# base.net
KiCad netlist of a schematic drawn in EAGLE
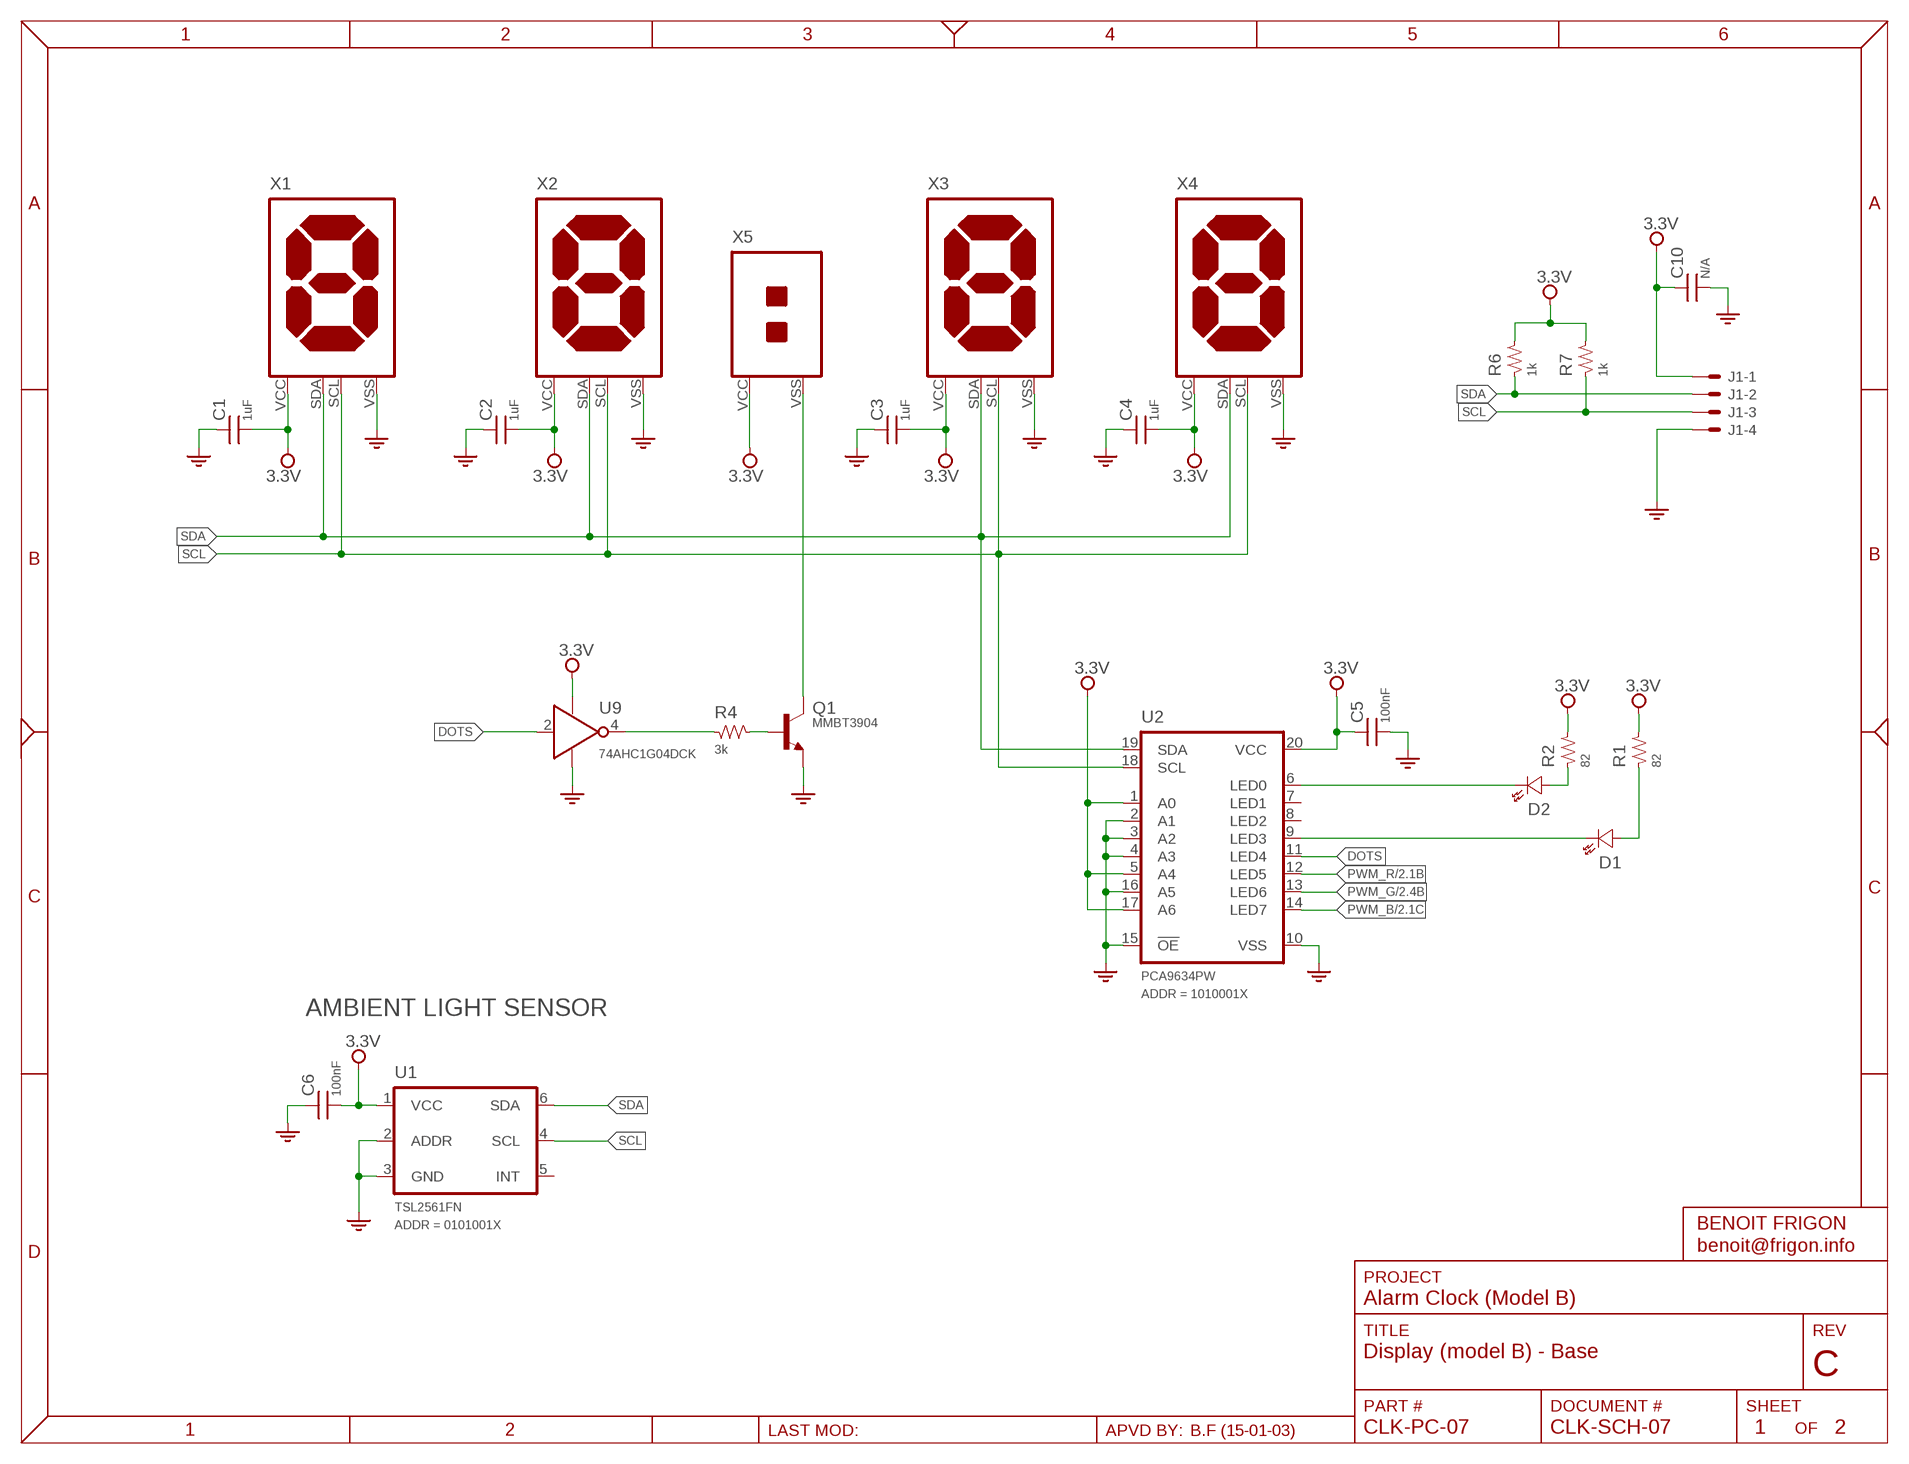
[diagram p0: schematic, sheet 1]
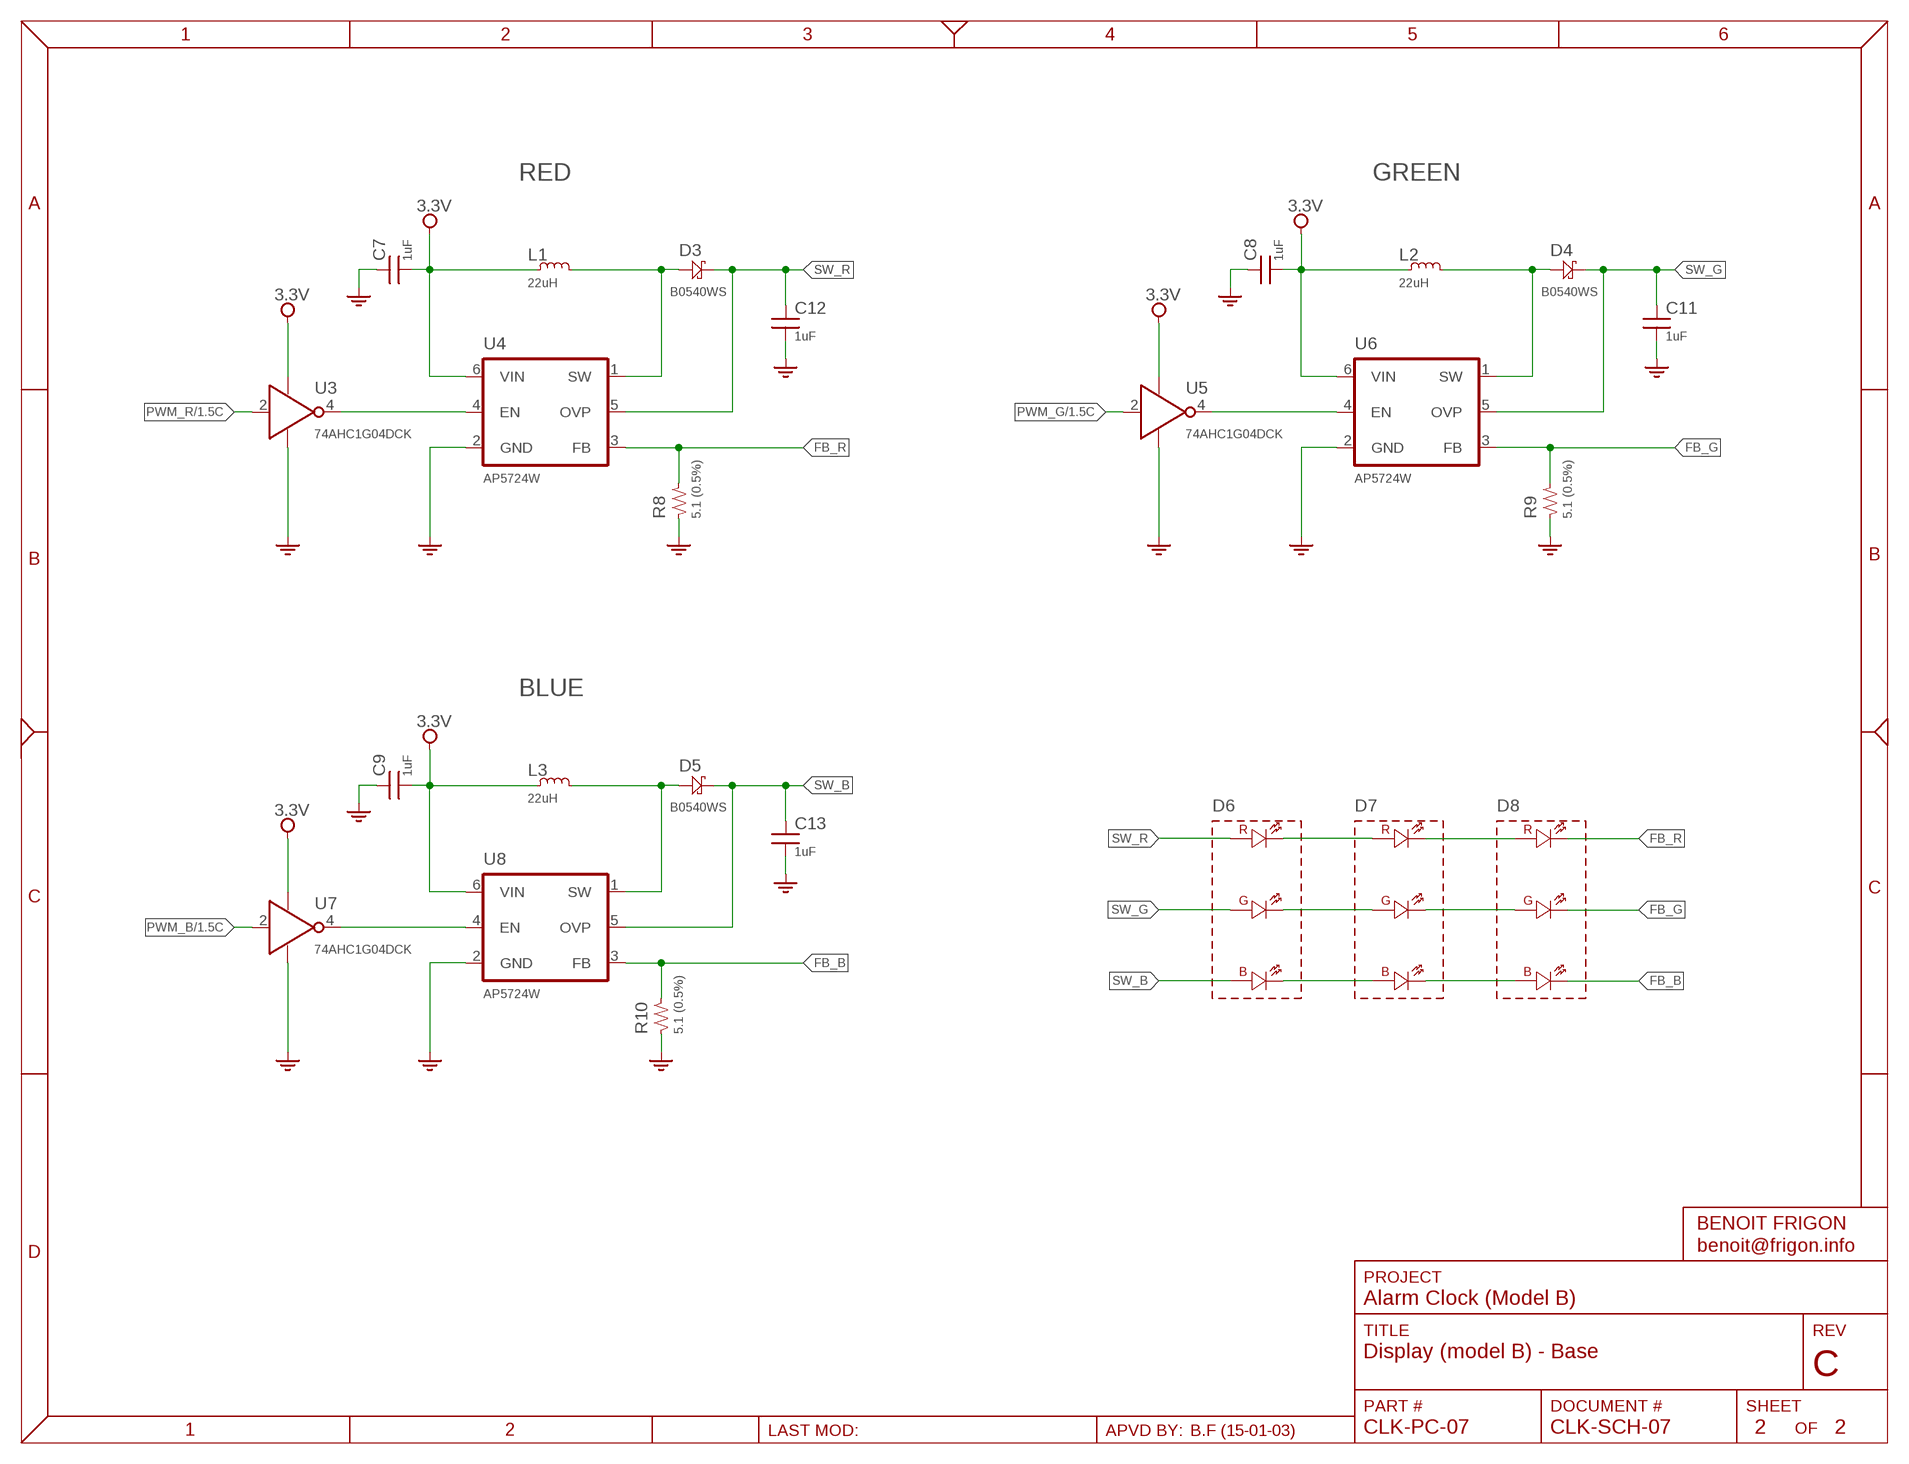
[diagram p1: schematic, sheet 2]

(export (version "E")
  (design (tool "Eeschema 10.0.6"))
  (components
    (comp (ref "C1")
      (value "1uF")
      (footprint "eagle-import:SMD_0603")
      (description "{DESCRIPTION} - SMT 0603 - {value}")
      (fields (field (name "PACKAGE") "SMT 0603"))
      (libsource (lib "eagle-import") (part "CAP-0603"))
    )
    (comp (ref "C2")
      (value "1uF")
      (footprint "eagle-import:SMD_0603")
      (description "{DESCRIPTION} - SMT 0603 - {value}")
      (fields (field (name "PACKAGE") "SMT 0603"))
      (libsource (lib "eagle-import") (part "CAP-0603"))
    )
    (comp (ref "C3")
      (value "1uF")
      (footprint "eagle-import:SMD_0603")
      (description "{DESCRIPTION} - SMT 0603 - {value}")
      (fields (field (name "PACKAGE") "SMT 0603"))
      (libsource (lib "eagle-import") (part "CAP-0603"))
    )
    (comp (ref "C4")
      (value "1uF")
      (footprint "eagle-import:SMD_0603")
      (description "{DESCRIPTION} - SMT 0603 - {value}")
      (fields (field (name "PACKAGE") "SMT 0603"))
      (libsource (lib "eagle-import") (part "CAP-0603"))
    )
    (comp (ref "C5")
      (value "100nF")
      (footprint "eagle-import:SMD_0603")
      (libsource (lib "eagle-import") (part "CAP-0603"))
    )
    (comp (ref "C6")
      (value "100nF")
      (footprint "eagle-import:SMD_0603")
      (libsource (lib "eagle-import") (part "CAP-0603"))
    )
    (comp (ref "C10")
      (value "N/A")
      (footprint "eagle-import:SMD_0805")
      (description "{DESCRIPTION} - SMT 0805 - {value}")
      (fields (field (name "PACKAGE") "SMT 0805"))
      (libsource (lib "eagle-import") (part "CAP-0805"))
    )
    (comp (ref "D1")
      (value "{ATTR:COLOR}")
      (footprint "eagle-import:LED_3MM")
      (description "{DESCRIPTION} T1 (3mm) - {ATTR:COLOR}")
      (fields (field (name "COLOR") "Green") (field (name "PACKAGE") "T1") (field (name "SKU") "-"))
      (libsource (lib "eagle-import") (part "LED-T1"))
    )
    (comp (ref "D2")
      (value "{ATTR:COLOR}")
      (footprint "eagle-import:LED_3MM")
      (libsource (lib "eagle-import") (part "LED-T1"))
    )
    (comp (ref "J1")
      (value "SNG-2MM-HEADER-07-V")
      (footprint "eagle-import:DF3X-7P-2DSA")
      (fields
        (field (name "MFG") "Hirose Electronic")
        (field (name "PART_NO") "DF3A-7P-2DSA")
        (field (name "SKU") "H2099-ND")
        (field (name "PRICE") "0.37")
        (field (name "SUPPLIER") "Digi-Key")
      )
      (libsource (lib "eagle-import") (part "SNG-2MM-HEADER-07-V"))
    )
    (comp (ref "Q1")
      (value "MMBT3904")
      (footprint "eagle-import:SOT23")
      (libsource (lib "eagle-import") (part "MMBT3904"))
    )
    (comp (ref "R1")
      (value "82")
      (footprint "eagle-import:SMD_0603")
      (description "{DESCRIPTION} - SMT 0603 - {VALUE}")
      (fields (field (name "PACKAGE") "SMT 0603"))
      (libsource (lib "eagle-import") (part "RES-0603"))
    )
    (comp (ref "R2")
      (value "82")
      (footprint "eagle-import:SMD_0603")
      (libsource (lib "eagle-import") (part "RES-0603"))
    )
    (comp (ref "R4")
      (value "3k")
      (footprint "eagle-import:SMD_0603")
      (description "{DESCRIPTION} - SMT 0603 - {VALUE}")
      (fields (field (name "PACKAGE") "SMT 0603"))
      (libsource (lib "eagle-import") (part "RES-0603"))
    )
    (comp (ref "R6")
      (value "1k")
      (footprint "eagle-import:SMD_0603")
      (libsource (lib "eagle-import") (part "RES-0603"))
    )
    (comp (ref "R7")
      (value "1k")
      (footprint "eagle-import:SMD_0603")
      (libsource (lib "eagle-import") (part "RES-0603"))
    )
    (comp (ref "U1")
      (value "TSL2561FN")
      (footprint "eagle-import:DFN-6")
      (fields (field (name "ADDR") "0101001X"))
      (libsource (lib "eagle-import") (part "TSL2561FN"))
    )
    (comp (ref "U2")
      (value "PCA9634PW")
      (footprint "eagle-import:TSSOP20")
      (fields (field (name "MFG") "NXP Semiconductors") (field (name "ADDR") "1010001X"))
      (libsource (lib "eagle-import") (part "PCA9634PW"))
    )
    (comp (ref "U9")
      (value "74AHC1G04DCK")
      (footprint "eagle-import:SC70-5")
      (libsource (lib "eagle-import") (part "741G04DCKAHC"))
    )
    (comp (ref "X1")
      (value "CLOCK_LED_SEGMENT")
      (footprint "eagle-import:CLOCK_LED_SEGMENT")
      (libsource (lib "eagle-import") (part "CLOCK_LED_SEGMENT"))
    )
    (comp (ref "X2")
      (value "CLOCK_LED_SEGMENT")
      (footprint "eagle-import:CLOCK_LED_SEGMENT")
      (libsource (lib "eagle-import") (part "CLOCK_LED_SEGMENT"))
    )
    (comp (ref "X3")
      (value "CLOCK_LED_SEGMENT")
      (footprint "eagle-import:CLOCK_LED_SEGMENT")
      (libsource (lib "eagle-import") (part "CLOCK_LED_SEGMENT"))
    )
    (comp (ref "X4")
      (value "CLOCK_LED_SEGMENT")
      (footprint "eagle-import:CLOCK_LED_SEGMENT")
      (libsource (lib "eagle-import") (part "CLOCK_LED_SEGMENT"))
    )
    (comp (ref "X5")
      (value "CLOCK_LED_DOTS")
      (footprint "eagle-import:CLOCK_LED_DOTS")
      (libsource (lib "eagle-import") (part "CLOCK_LED_DOTS"))
    )
    (comp (ref "C7")
      (value "1uF")
      (footprint "eagle-import:SMD_0603")
      (description "{DESCRIPTION} - SMT 0603 - {value}")
      (fields (field (name "PACKAGE") "SMT 0603"))
      (libsource (lib "eagle-import") (part "CAP-0603"))
    )
    (comp (ref "C8")
      (value "1uF")
      (footprint "eagle-import:SMD_0603")
      (description "{DESCRIPTION} - SMT 0603 - {value}")
      (fields (field (name "PACKAGE") "SMT 0603"))
      (libsource (lib "eagle-import") (part "CAP-0603"))
    )
    (comp (ref "C9")
      (value "1uF")
      (footprint "eagle-import:SMD_0603")
      (description "{DESCRIPTION} - SMT 0603 - {value}")
      (fields (field (name "PACKAGE") "SMT 0603"))
      (libsource (lib "eagle-import") (part "CAP-0603"))
    )
    (comp (ref "C11")
      (value "1uF")
      (footprint "eagle-import:SMD_0603")
      (description "{DESCRIPTION} - SMT 0603 - {value}")
      (fields (field (name "PACKAGE") "SMT 0603"))
      (libsource (lib "eagle-import") (part "CAP-0603"))
    )
    (comp (ref "C12")
      (value "1uF")
      (footprint "eagle-import:SMD_0603")
      (description "{DESCRIPTION} - SMT 0603 - {value}")
      (fields (field (name "PACKAGE") "SMT 0603"))
      (libsource (lib "eagle-import") (part "CAP-0603"))
    )
    (comp (ref "C13")
      (value "1uF")
      (footprint "eagle-import:SMD_0603")
      (description "{DESCRIPTION} - SMT 0603 - {value}")
      (fields (field (name "PACKAGE") "SMT 0603"))
      (libsource (lib "eagle-import") (part "CAP-0603"))
    )
    (comp (ref "D3")
      (value "DIODE_SCHOTTKY-SOD323")
      (footprint "eagle-import:SOD-323")
      (fields (field (name "PART_NO") "B0540WS"))
      (libsource (lib "eagle-import") (part "DIODE_SCHOTTKY-SOD323"))
    )
    (comp (ref "D4")
      (value "DIODE_SCHOTTKY-SOD323")
      (footprint "eagle-import:SOD-323")
      (fields (field (name "PART_NO") "B0540WS"))
      (libsource (lib "eagle-import") (part "DIODE_SCHOTTKY-SOD323"))
    )
    (comp (ref "D5")
      (value "DIODE_SCHOTTKY-SOD323")
      (footprint "eagle-import:SOD-323")
      (fields (field (name "PART_NO") "B0540WS"))
      (libsource (lib "eagle-import") (part "DIODE_SCHOTTKY-SOD323"))
    )
    (comp (ref "D6")
      (value "SMP6-RGB")
      (footprint "eagle-import:LED_RGB_PLCC6")
      (fields (field (name "MFG") "Bivar") (field (name "SKU") "SMP6-RGB"))
      (libsource (lib "eagle-import") (part "SMP6-RGB"))
    )
    (comp (ref "D7")
      (value "SMP6-RGB")
      (footprint "eagle-import:LED_RGB_PLCC6")
      (fields (field (name "MFG") "Bivar"))
      (libsource (lib "eagle-import") (part "SMP6-RGB"))
    )
    (comp (ref "D8")
      (value "SMP6-RGB")
      (footprint "eagle-import:LED_RGB_PLCC6")
      (fields (field (name "MFG") "Bivar"))
      (libsource (lib "eagle-import") (part "SMP6-RGB"))
    )
    (comp (ref "L1")
      (value "22uH")
      (footprint "eagle-import:IND-4X4")
      (fields (field (name "PART_NO") "NR4012T220M"))
      (libsource (lib "eagle-import") (part "IND?-4X4"))
    )
    (comp (ref "L2")
      (value "22uH")
      (footprint "eagle-import:IND-4X4")
      (fields (field (name "PART_NO") "NR4012T220M"))
      (libsource (lib "eagle-import") (part "IND?-4X4"))
    )
    (comp (ref "L3")
      (value "22uH")
      (footprint "eagle-import:IND-4X4")
      (fields (field (name "PART_NO") "NR4012T220M"))
      (libsource (lib "eagle-import") (part "IND?-4X4"))
    )
    (comp (ref "R8")
      (value "5.1 (0.5%)")
      (footprint "eagle-import:SMD_0603")
      (description "{DESCRIPTION} - SMT 0603 - {VALUE}")
      (fields (field (name "PACKAGE") "SMT 0603"))
      (libsource (lib "eagle-import") (part "RES-0603"))
    )
    (comp (ref "R9")
      (value "5.1 (0.5%)")
      (footprint "eagle-import:SMD_0603")
      (libsource (lib "eagle-import") (part "RES-0603"))
    )
    (comp (ref "R10")
      (value "5.1 (0.5%)")
      (footprint "eagle-import:SMD_0603")
      (description "{DESCRIPTION} - SMT 0603 - {VALUE}")
      (fields (field (name "PACKAGE") "SMT 0603"))
      (libsource (lib "eagle-import") (part "RES-0603"))
    )
    (comp (ref "U3")
      (value "74AHC1G04DCK")
      (footprint "eagle-import:SC70-5")
      (libsource (lib "eagle-import") (part "741G04DCKAHC"))
    )
    (comp (ref "U4")
      (value "AP5724W")
      (footprint "eagle-import:SOT23-6")
      (fields (field (name "MFG") "Diodes Inc."))
      (libsource (lib "eagle-import") (part "AP5724W"))
    )
    (comp (ref "U5")
      (value "74AHC1G04DCK")
      (footprint "eagle-import:SC70-5")
      (libsource (lib "eagle-import") (part "741G04DCKAHC"))
    )
    (comp (ref "U6")
      (value "AP5724W")
      (footprint "eagle-import:SOT23-6")
      (fields (field (name "MFG") "Diodes Inc."))
      (libsource (lib "eagle-import") (part "AP5724W"))
    )
    (comp (ref "U7")
      (value "74AHC1G04DCK")
      (footprint "eagle-import:SC70-5")
      (libsource (lib "eagle-import") (part "741G04DCKAHC"))
    )
    (comp (ref "U8")
      (value "AP5724W")
      (footprint "eagle-import:SOT23-6")
      (fields (field (name "MFG") "Diodes Inc."))
      (libsource (lib "eagle-import") (part "AP5724W"))
    )
  )
  (nets
    (net (code "1") (name "3.3V") (class "Default")
      (node (ref "C1") (pin "2") (pinfunction "2_2") (pintype "passive"))
      (node (ref "C10") (pin "1") (pinfunction "1_1") (pintype "passive"))
      (node (ref "C2") (pin "2") (pinfunction "2_2") (pintype "passive"))
      (node (ref "C3") (pin "2") (pinfunction "2_2") (pintype "passive"))
      (node (ref "C4") (pin "2") (pinfunction "2_2") (pintype "passive"))
      (node (ref "C5") (pin "1") (pinfunction "1_1") (pintype "passive"))
      (node (ref "C6") (pin "2") (pinfunction "2_2") (pintype "passive"))
      (node (ref "C7") (pin "2") (pinfunction "2_2") (pintype "passive"))
      (node (ref "C8") (pin "2") (pinfunction "2_2") (pintype "passive"))
      (node (ref "C9") (pin "2") (pinfunction "2_2") (pintype "passive"))
      (node (ref "J1") (pin "1") (pinfunction "S_1") (pintype "bidirectional"))
      (node (ref "L1") (pin "1") (pinfunction "1_1") (pintype "passive"))
      (node (ref "L2") (pin "1") (pinfunction "1_1") (pintype "passive"))
      (node (ref "L3") (pin "1") (pinfunction "1_1") (pintype "passive"))
      (node (ref "R1") (pin "2") (pinfunction "2_2") (pintype "passive"))
      (node (ref "R2") (pin "2") (pinfunction "2_2") (pintype "passive"))
      (node (ref "R6") (pin "2") (pinfunction "2_2") (pintype "passive"))
      (node (ref "R7") (pin "2") (pinfunction "2_2") (pintype "passive"))
      (node (ref "U1") (pin "1") (pinfunction "VCC_1") (pintype "bidirectional"))
      (node (ref "U2") (pin "1") (pinfunction "A0_1") (pintype "bidirectional"))
      (node (ref "U2") (pin "17") (pinfunction "A6_17") (pintype "bidirectional"))
      (node (ref "U2") (pin "20") (pinfunction "VCC_20") (pintype "bidirectional"))
      (node (ref "U2") (pin "5") (pinfunction "A4_5") (pintype "bidirectional"))
      (node (ref "U3") (pin "5") (pinfunction "VCC_5") (pintype "power_in"))
      (node (ref "U4") (pin "6") (pinfunction "VIN_6") (pintype "power_in"))
      (node (ref "U5") (pin "5") (pinfunction "VCC_5") (pintype "power_in"))
      (node (ref "U6") (pin "6") (pinfunction "VIN_6") (pintype "power_in"))
      (node (ref "U7") (pin "5") (pinfunction "VCC_5") (pintype "power_in"))
      (node (ref "U8") (pin "6") (pinfunction "VIN_6") (pintype "power_in"))
      (node (ref "U9") (pin "5") (pinfunction "VCC_5") (pintype "power_in"))
      (node (ref "X1") (pin "VCC") (pinfunction "VCC_VCC") (pintype "bidirectional"))
      (node (ref "X2") (pin "VCC") (pinfunction "VCC_VCC") (pintype "bidirectional"))
      (node (ref "X3") (pin "VCC") (pinfunction "VCC_VCC") (pintype "bidirectional"))
      (node (ref "X4") (pin "VCC") (pinfunction "VCC_VCC") (pintype "bidirectional"))
      (node (ref "X5") (pin "VCC") (pinfunction "VCC_VCC") (pintype "bidirectional"))
    )
    (net (code "2") (name "DOTS") (class "Default")
      (node (ref "U2") (pin "11") (pinfunction "LED4_11") (pintype "bidirectional"))
      (node (ref "U9") (pin "2") (pinfunction "A_2") (pintype "input"))
    )
    (net (code "3") (name "FB_B") (class "Default")
      (node (ref "D8") (pin "5") (pinfunction "BK_5") (pintype "passive"))
      (node (ref "R10") (pin "2") (pinfunction "2_2") (pintype "passive"))
      (node (ref "U8") (pin "3") (pinfunction "FB_3") (pintype "input"))
    )
    (net (code "4") (name "FB_G") (class "Default")
      (node (ref "D8") (pin "1") (pinfunction "GK_1") (pintype "passive"))
      (node (ref "R9") (pin "2") (pinfunction "2_2") (pintype "passive"))
      (node (ref "U6") (pin "3") (pinfunction "FB_3") (pintype "input"))
    )
    (net (code "5") (name "FB_R") (class "Default")
      (node (ref "D8") (pin "3") (pinfunction "RK_3") (pintype "passive"))
      (node (ref "R8") (pin "2") (pinfunction "2_2") (pintype "passive"))
      (node (ref "U4") (pin "3") (pinfunction "FB_3") (pintype "input"))
    )
    (net (code "6") (name "GND") (class "Default")
      (node (ref "C1") (pin "1") (pinfunction "1_1") (pintype "passive"))
      (node (ref "C10") (pin "2") (pinfunction "2_2") (pintype "passive"))
      (node (ref "C11") (pin "2") (pinfunction "2_2") (pintype "passive"))
      (node (ref "C12") (pin "2") (pinfunction "2_2") (pintype "passive"))
      (node (ref "C13") (pin "2") (pinfunction "2_2") (pintype "passive"))
      (node (ref "C2") (pin "1") (pinfunction "1_1") (pintype "passive"))
      (node (ref "C3") (pin "1") (pinfunction "1_1") (pintype "passive"))
      (node (ref "C4") (pin "1") (pinfunction "1_1") (pintype "passive"))
      (node (ref "C5") (pin "2") (pinfunction "2_2") (pintype "passive"))
      (node (ref "C6") (pin "1") (pinfunction "1_1") (pintype "passive"))
      (node (ref "C7") (pin "1") (pinfunction "1_1") (pintype "passive"))
      (node (ref "C8") (pin "1") (pinfunction "1_1") (pintype "passive"))
      (node (ref "C9") (pin "1") (pinfunction "1_1") (pintype "passive"))
      (node (ref "J1") (pin "4") (pinfunction "S_4") (pintype "bidirectional"))
      (node (ref "Q1") (pin "2") (pinfunction "E_2") (pintype "passive"))
      (node (ref "R10") (pin "1") (pinfunction "1_1") (pintype "passive"))
      (node (ref "R8") (pin "1") (pinfunction "1_1") (pintype "passive"))
      (node (ref "R9") (pin "1") (pinfunction "1_1") (pintype "passive"))
      (node (ref "U1") (pin "2") (pinfunction "ADDR_2") (pintype "bidirectional"))
      (node (ref "U1") (pin "3") (pinfunction "GND_3") (pintype "bidirectional"))
      (node (ref "U2") (pin "10") (pinfunction "VSS_10") (pintype "bidirectional"))
      (node (ref "U2") (pin "15") (pinfunction "~{OE}_15") (pintype "bidirectional"))
      (node (ref "U2") (pin "16") (pinfunction "A5_16") (pintype "bidirectional"))
      (node (ref "U2") (pin "2") (pinfunction "A1_2") (pintype "bidirectional"))
      (node (ref "U2") (pin "3") (pinfunction "A2_3") (pintype "bidirectional"))
      (node (ref "U2") (pin "4") (pinfunction "A3_4") (pintype "bidirectional"))
      (node (ref "U3") (pin "3") (pinfunction "GND_3") (pintype "power_in"))
      (node (ref "U4") (pin "2") (pinfunction "GND_2") (pintype "power_in"))
      (node (ref "U5") (pin "3") (pinfunction "GND_3") (pintype "power_in"))
      (node (ref "U6") (pin "2") (pinfunction "GND_2") (pintype "power_in"))
      (node (ref "U7") (pin "3") (pinfunction "GND_3") (pintype "power_in"))
      (node (ref "U8") (pin "2") (pinfunction "GND_2") (pintype "power_in"))
      (node (ref "U9") (pin "3") (pinfunction "GND_3") (pintype "power_in"))
      (node (ref "X1") (pin "VSS") (pinfunction "VSS_VSS") (pintype "bidirectional"))
      (node (ref "X2") (pin "VSS") (pinfunction "VSS_VSS") (pintype "bidirectional"))
      (node (ref "X3") (pin "VSS") (pinfunction "VSS_VSS") (pintype "bidirectional"))
      (node (ref "X4") (pin "VSS") (pinfunction "VSS_VSS") (pintype "bidirectional"))
    )
    (net (code "7") (name "Net-(D1-PadA)") (class "Default")
      (node (ref "D1") (pin "A") (pinfunction "A_A") (pintype "passive"))
      (node (ref "R1") (pin "1") (pinfunction "1_1") (pintype "passive"))
    )
    (net (code "8") (name "Net-(D2-PadA)") (class "Default")
      (node (ref "D2") (pin "A") (pinfunction "A_A") (pintype "passive"))
      (node (ref "R2") (pin "1") (pinfunction "1_1") (pintype "passive"))
    )
    (net (code "9") (name "Net-(D6-BK)") (class "Default")
      (node (ref "D6") (pin "5") (pinfunction "BK_5") (pintype "passive"))
      (node (ref "D7") (pin "6") (pinfunction "BA_6") (pintype "passive"))
    )
    (net (code "10") (name "Net-(D6-GK)") (class "Default")
      (node (ref "D6") (pin "1") (pinfunction "GK_1") (pintype "passive"))
      (node (ref "D7") (pin "2") (pinfunction "GA_2") (pintype "passive"))
    )
    (net (code "11") (name "Net-(D6-RK)") (class "Default")
      (node (ref "D6") (pin "3") (pinfunction "RK_3") (pintype "passive"))
      (node (ref "D7") (pin "4") (pinfunction "RA_4") (pintype "passive"))
    )
    (net (code "12") (name "Net-(D7-BK)") (class "Default")
      (node (ref "D7") (pin "5") (pinfunction "BK_5") (pintype "passive"))
      (node (ref "D8") (pin "6") (pinfunction "BA_6") (pintype "passive"))
    )
    (net (code "13") (name "Net-(D7-GK)") (class "Default")
      (node (ref "D7") (pin "1") (pinfunction "GK_1") (pintype "passive"))
      (node (ref "D8") (pin "2") (pinfunction "GA_2") (pintype "passive"))
    )
    (net (code "14") (name "Net-(D7-RK)") (class "Default")
      (node (ref "D7") (pin "3") (pinfunction "RK_3") (pintype "passive"))
      (node (ref "D8") (pin "4") (pinfunction "RA_4") (pintype "passive"))
    )
    (net (code "15") (name "Net-(Q1-B)") (class "Default")
      (node (ref "Q1") (pin "1") (pinfunction "B_1") (pintype "passive"))
      (node (ref "R4") (pin "2") (pinfunction "2_2") (pintype "passive"))
    )
    (net (code "16") (name "Net-(Q1-C)") (class "Default")
      (node (ref "Q1") (pin "3") (pinfunction "C_3") (pintype "passive"))
      (node (ref "X5") (pin "VSS") (pinfunction "VSS_VSS") (pintype "bidirectional"))
    )
    (net (code "17") (name "Net-(U2-LED0)") (class "Default")
      (node (ref "D2") (pin "K") (pinfunction "K_K") (pintype "passive"))
      (node (ref "U2") (pin "6") (pinfunction "LED0_6") (pintype "bidirectional"))
    )
    (net (code "18") (name "Net-(U2-LED3)") (class "Default")
      (node (ref "D1") (pin "K") (pinfunction "K_K") (pintype "passive"))
      (node (ref "U2") (pin "9") (pinfunction "LED3_9") (pintype "bidirectional"))
    )
    (net (code "19") (name "Net-(U3-Y)") (class "Default")
      (node (ref "U3") (pin "4") (pinfunction "Y_4") (pintype "output"))
      (node (ref "U4") (pin "4") (pinfunction "EN_4") (pintype "input"))
    )
    (net (code "20") (name "Net-(U4-SW)") (class "Default")
      (node (ref "D3") (pin "A") (pinfunction "A_A") (pintype "passive"))
      (node (ref "L1") (pin "2") (pinfunction "2_2") (pintype "passive"))
      (node (ref "U4") (pin "1") (pinfunction "SW_1") (pintype "passive"))
    )
    (net (code "21") (name "Net-(U5-Y)") (class "Default")
      (node (ref "U5") (pin "4") (pinfunction "Y_4") (pintype "output"))
      (node (ref "U6") (pin "4") (pinfunction "EN_4") (pintype "input"))
    )
    (net (code "22") (name "Net-(U6-SW)") (class "Default")
      (node (ref "D4") (pin "A") (pinfunction "A_A") (pintype "passive"))
      (node (ref "L2") (pin "2") (pinfunction "2_2") (pintype "passive"))
      (node (ref "U6") (pin "1") (pinfunction "SW_1") (pintype "passive"))
    )
    (net (code "23") (name "Net-(U7-Y)") (class "Default")
      (node (ref "U7") (pin "4") (pinfunction "Y_4") (pintype "output"))
      (node (ref "U8") (pin "4") (pinfunction "EN_4") (pintype "input"))
    )
    (net (code "24") (name "Net-(U8-SW)") (class "Default")
      (node (ref "D5") (pin "A") (pinfunction "A_A") (pintype "passive"))
      (node (ref "L3") (pin "2") (pinfunction "2_2") (pintype "passive"))
      (node (ref "U8") (pin "1") (pinfunction "SW_1") (pintype "passive"))
    )
    (net (code "25") (name "Net-(U9-Y)") (class "Default")
      (node (ref "R4") (pin "1") (pinfunction "1_1") (pintype "passive"))
      (node (ref "U9") (pin "4") (pinfunction "Y_4") (pintype "output"))
    )
    (net (code "26") (name "PWM_B") (class "Default")
      (node (ref "U2") (pin "14") (pinfunction "LED7_14") (pintype "bidirectional"))
      (node (ref "U7") (pin "2") (pinfunction "A_2") (pintype "input"))
    )
    (net (code "27") (name "PWM_G") (class "Default")
      (node (ref "U2") (pin "13") (pinfunction "LED6_13") (pintype "bidirectional"))
      (node (ref "U5") (pin "2") (pinfunction "A_2") (pintype "input"))
    )
    (net (code "28") (name "PWM_R") (class "Default")
      (node (ref "U2") (pin "12") (pinfunction "LED5_12") (pintype "bidirectional"))
      (node (ref "U3") (pin "2") (pinfunction "A_2") (pintype "input"))
    )
    (net (code "29") (name "SCL") (class "Default")
      (node (ref "J1") (pin "3") (pinfunction "S_3") (pintype "bidirectional"))
      (node (ref "R7") (pin "1") (pinfunction "1_1") (pintype "passive"))
      (node (ref "U1") (pin "4") (pinfunction "SCL_4") (pintype "bidirectional"))
      (node (ref "U2") (pin "18") (pinfunction "SCL_18") (pintype "bidirectional"))
      (node (ref "X1") (pin "SCL") (pinfunction "SCL_SCL") (pintype "bidirectional"))
      (node (ref "X2") (pin "SCL") (pinfunction "SCL_SCL") (pintype "bidirectional"))
      (node (ref "X3") (pin "SCL") (pinfunction "SCL_SCL") (pintype "bidirectional"))
      (node (ref "X4") (pin "SCL") (pinfunction "SCL_SCL") (pintype "bidirectional"))
    )
    (net (code "30") (name "SDA") (class "Default")
      (node (ref "J1") (pin "2") (pinfunction "S_2") (pintype "bidirectional"))
      (node (ref "R6") (pin "1") (pinfunction "1_1") (pintype "passive"))
      (node (ref "U1") (pin "6") (pinfunction "SDA_6") (pintype "bidirectional"))
      (node (ref "U2") (pin "19") (pinfunction "SDA_19") (pintype "bidirectional"))
      (node (ref "X1") (pin "SDA") (pinfunction "SDA_SDA") (pintype "bidirectional"))
      (node (ref "X2") (pin "SDA") (pinfunction "SDA_SDA") (pintype "bidirectional"))
      (node (ref "X3") (pin "SDA") (pinfunction "SDA_SDA") (pintype "bidirectional"))
      (node (ref "X4") (pin "SDA") (pinfunction "SDA_SDA") (pintype "bidirectional"))
    )
    (net (code "31") (name "SW_B") (class "Default")
      (node (ref "C13") (pin "1") (pinfunction "1_1") (pintype "passive"))
      (node (ref "D5") (pin "K") (pinfunction "K_K") (pintype "passive"))
      (node (ref "D6") (pin "6") (pinfunction "BA_6") (pintype "passive"))
      (node (ref "U8") (pin "5") (pinfunction "OVP_5") (pintype "input"))
    )
    (net (code "32") (name "SW_G") (class "Default")
      (node (ref "C11") (pin "1") (pinfunction "1_1") (pintype "passive"))
      (node (ref "D4") (pin "K") (pinfunction "K_K") (pintype "passive"))
      (node (ref "D6") (pin "2") (pinfunction "GA_2") (pintype "passive"))
      (node (ref "U6") (pin "5") (pinfunction "OVP_5") (pintype "input"))
    )
    (net (code "33") (name "SW_R") (class "Default")
      (node (ref "C12") (pin "1") (pinfunction "1_1") (pintype "passive"))
      (node (ref "D3") (pin "K") (pinfunction "K_K") (pintype "passive"))
      (node (ref "D6") (pin "4") (pinfunction "RA_4") (pintype "passive"))
      (node (ref "U4") (pin "5") (pinfunction "OVP_5") (pintype "input"))
    )
    (net (code "34") (name "unconnected-(U1-INT-Pad5)") (class "Default")
      (node (ref "U1") (pin "5") (pinfunction "INT_5") (pintype "bidirectional"))
    )
    (net (code "35") (name "unconnected-(U2-LED1-Pad7)") (class "Default")
      (node (ref "U2") (pin "7") (pinfunction "LED1_7") (pintype "bidirectional"))
    )
    (net (code "36") (name "unconnected-(U2-LED2-Pad8)") (class "Default")
      (node (ref "U2") (pin "8") (pinfunction "LED2_8") (pintype "bidirectional"))
    )
  )
)
